# grids_v02.net
KiCad netlist of a schematic drawn in EAGLE
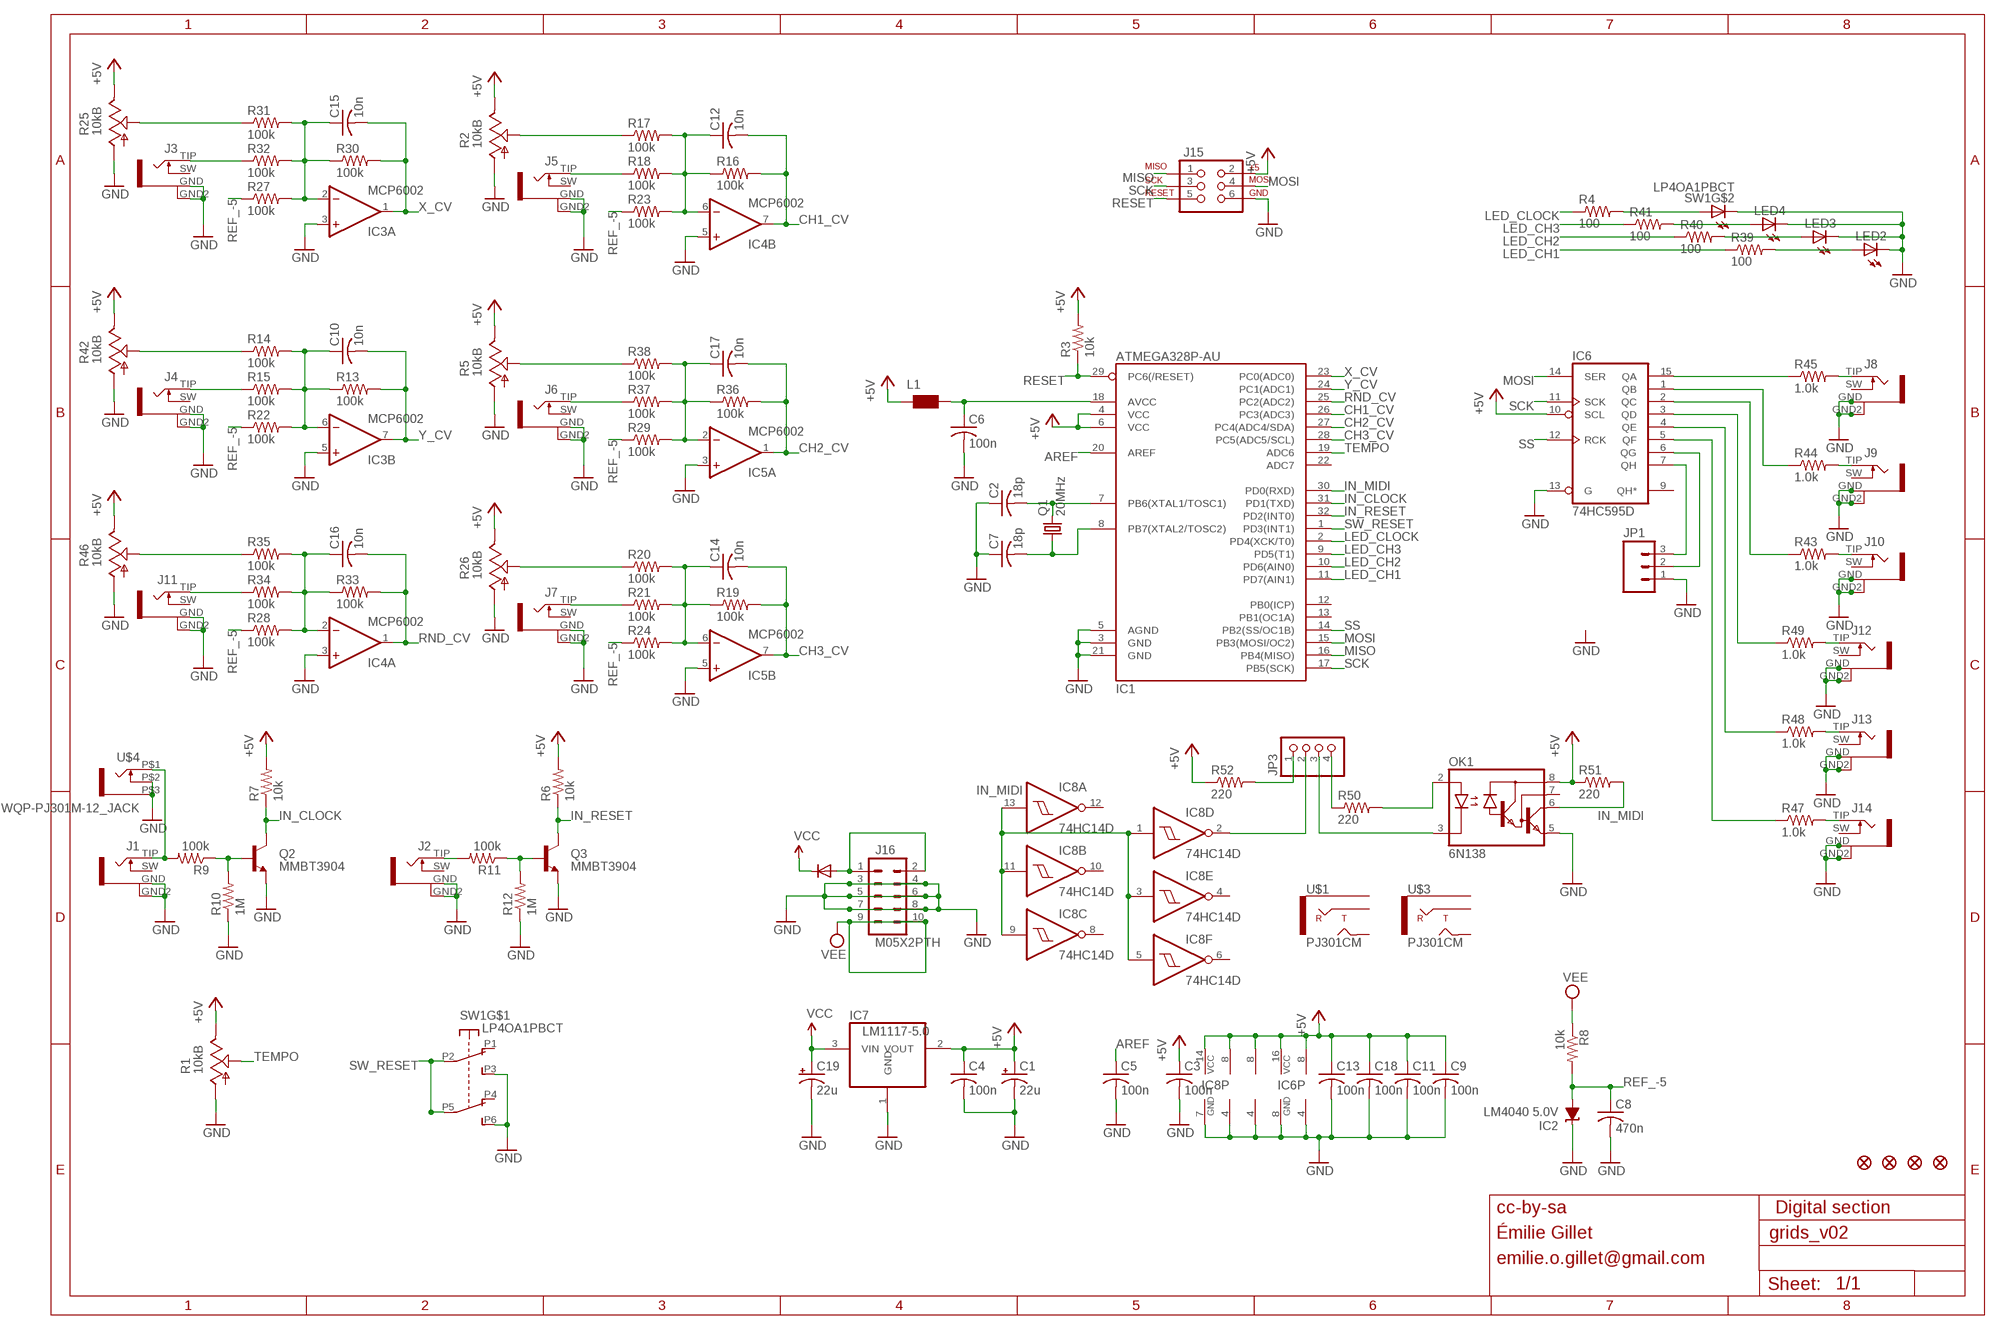
[diagram p0: schematic, sheet 1]

(export (version "E")
  (design (tool "Eeschema 10.0.6"))
  (components
    (comp (ref "C1")
      (value "22u")
      (footprint "eagle-import:PANASONIC_C")
      (libsource (lib "eagle-import") (part "CPOL-USC"))
    )
    (comp (ref "C2")
      (value "18p")
      (footprint "eagle-import:C0603")
      (libsource (lib "eagle-import") (part "C-USC0603"))
    )
    (comp (ref "C3")
      (value "100n")
      (footprint "eagle-import:C0603")
      (libsource (lib "eagle-import") (part "C-USC0603"))
    )
    (comp (ref "C4")
      (value "100n")
      (footprint "eagle-import:C0603")
      (libsource (lib "eagle-import") (part "C-USC0603"))
    )
    (comp (ref "C5")
      (value "100n")
      (footprint "eagle-import:C0603")
      (libsource (lib "eagle-import") (part "C-USC0603"))
    )
    (comp (ref "C6")
      (value "100n")
      (footprint "eagle-import:C0603")
      (libsource (lib "eagle-import") (part "C-USC0603"))
    )
    (comp (ref "C7")
      (value "18p")
      (footprint "eagle-import:C0603")
      (libsource (lib "eagle-import") (part "C-USC0603"))
    )
    (comp (ref "C8")
      (value "470n")
      (footprint "eagle-import:C0603")
      (libsource (lib "eagle-import") (part "C-USC0603"))
    )
    (comp (ref "C9")
      (value "100n")
      (footprint "eagle-import:C0603")
      (libsource (lib "eagle-import") (part "C-USC0603"))
    )
    (comp (ref "C10")
      (value "10n")
      (footprint "eagle-import:C0603")
      (libsource (lib "eagle-import") (part "C-USC0603"))
    )
    (comp (ref "C11")
      (value "100n")
      (footprint "eagle-import:C0603")
      (libsource (lib "eagle-import") (part "C-USC0603"))
    )
    (comp (ref "C12")
      (value "10n")
      (footprint "eagle-import:C0603")
      (libsource (lib "eagle-import") (part "C-USC0603"))
    )
    (comp (ref "C13")
      (value "100n")
      (footprint "eagle-import:C0603")
      (libsource (lib "eagle-import") (part "C-USC0603"))
    )
    (comp (ref "C14")
      (value "10n")
      (footprint "eagle-import:C0603")
      (libsource (lib "eagle-import") (part "C-USC0603"))
    )
    (comp (ref "C15")
      (value "10n")
      (footprint "eagle-import:C0603")
      (libsource (lib "eagle-import") (part "C-USC0603"))
    )
    (comp (ref "C16")
      (value "10n")
      (footprint "eagle-import:C0603")
      (libsource (lib "eagle-import") (part "C-USC0603"))
    )
    (comp (ref "C17")
      (value "10n")
      (footprint "eagle-import:C0603")
      (libsource (lib "eagle-import") (part "C-USC0603"))
    )
    (comp (ref "C18")
      (value "100n")
      (footprint "eagle-import:C0603")
      (libsource (lib "eagle-import") (part "C-USC0603"))
    )
    (comp (ref "C19")
      (value "22u")
      (footprint "eagle-import:PANASONIC_C")
      (libsource (lib "eagle-import") (part "CPOL-USC"))
    )
    (comp (ref "D1")
      (value "1N5819HW")
      (footprint "eagle-import:SOD123")
      (libsource (lib "eagle-import") (part "DIODE-SOD123"))
    )
    (comp (ref "F1")
      (value "FIDUCIAL1X2")
      (footprint "eagle-import:FIDUCIAL-1X2")
      (libsource (lib "eagle-import") (part "FIDUCIAL1X2"))
    )
    (comp (ref "F2")
      (value "FIDUCIAL1X2")
      (footprint "eagle-import:FIDUCIAL-1X2")
      (libsource (lib "eagle-import") (part "FIDUCIAL1X2"))
    )
    (comp (ref "F3")
      (value "FIDUCIAL1X2")
      (footprint "eagle-import:FIDUCIAL-1X2")
      (libsource (lib "eagle-import") (part "FIDUCIAL1X2"))
    )
    (comp (ref "F4")
      (value "FIDUCIAL1X2")
      (footprint "eagle-import:FIDUCIAL-1X2")
      (libsource (lib "eagle-import") (part "FIDUCIAL1X2"))
    )
    (comp (ref "IC1")
      (value "ATMEGA328P-AU")
      (footprint "eagle-import:TQFP32-08")
      (libsource (lib "eagle-import") (part "ATMEGA168"))
    )
    (comp (ref "IC2")
      (value "LM4040 5.0V")
      (footprint "eagle-import:DBZ_R-PDSO-G3")
      (libsource (lib "eagle-import") (part "LM4041DBZC12"))
    )
    (comp (ref "IC3")
      (value "MCP6002")
      (footprint "eagle-import:SO08")
      (libsource (lib "eagle-import") (part "TL072D"))
    )
    (comp (ref "IC4")
      (value "MCP6002")
      (footprint "eagle-import:SO08")
      (libsource (lib "eagle-import") (part "TL072D"))
    )
    (comp (ref "IC5")
      (value "MCP6002")
      (footprint "eagle-import:SO08")
      (libsource (lib "eagle-import") (part "TL072D"))
    )
    (comp (ref "IC6")
      (value "74HC595D")
      (footprint "eagle-import:SO16")
      (libsource (lib "eagle-import") (part "74595DHC"))
    )
    (comp (ref "IC7")
      (value "LM1117-5.0")
      (footprint "eagle-import:SOT223")
      (libsource (lib "eagle-import") (part "REG1117"))
    )
    (comp (ref "IC8")
      (value "74HC14D")
      (footprint "eagle-import:SO14")
      (libsource (lib "eagle-import") (part "7414DHC"))
    )
    (comp (ref "J1")
      (value "PJ301WQP")
      (footprint "eagle-import:WQP_PJ_301BM")
      (libsource (lib "eagle-import") (part "PJ301WQP"))
    )
    (comp (ref "J2")
      (value "PJ301WQP")
      (footprint "eagle-import:WQP_PJ_301BM")
      (libsource (lib "eagle-import") (part "PJ301WQP"))
    )
    (comp (ref "J3")
      (value "PJ301WQP")
      (footprint "eagle-import:WQP_PJ_301BM")
      (libsource (lib "eagle-import") (part "PJ301WQP"))
    )
    (comp (ref "J4")
      (value "PJ301WQP")
      (footprint "eagle-import:WQP_PJ_301BM")
      (libsource (lib "eagle-import") (part "PJ301WQP"))
    )
    (comp (ref "J5")
      (value "PJ301WQP")
      (footprint "eagle-import:WQP_PJ_301BM")
      (libsource (lib "eagle-import") (part "PJ301WQP"))
    )
    (comp (ref "J6")
      (value "PJ301WQP")
      (footprint "eagle-import:WQP_PJ_301BM")
      (libsource (lib "eagle-import") (part "PJ301WQP"))
    )
    (comp (ref "J7")
      (value "PJ301WQP")
      (footprint "eagle-import:WQP_PJ_301BM")
      (libsource (lib "eagle-import") (part "PJ301WQP"))
    )
    (comp (ref "J8")
      (value "PJ301WQP")
      (footprint "eagle-import:WQP_PJ_301BM")
      (libsource (lib "eagle-import") (part "PJ301WQP"))
    )
    (comp (ref "J9")
      (value "PJ301WQP")
      (footprint "eagle-import:WQP_PJ_301BM")
      (libsource (lib "eagle-import") (part "PJ301WQP"))
    )
    (comp (ref "J10")
      (value "PJ301WQP")
      (footprint "eagle-import:WQP_PJ_301BM")
      (libsource (lib "eagle-import") (part "PJ301WQP"))
    )
    (comp (ref "J11")
      (value "PJ301WQP")
      (footprint "eagle-import:WQP_PJ_301BM")
      (libsource (lib "eagle-import") (part "PJ301WQP"))
    )
    (comp (ref "J12")
      (value "PJ301WQP")
      (footprint "eagle-import:WQP_PJ_301BM")
      (libsource (lib "eagle-import") (part "PJ301WQP"))
    )
    (comp (ref "J13")
      (value "PJ301WQP")
      (footprint "eagle-import:WQP_PJ_301BM")
      (libsource (lib "eagle-import") (part "PJ301WQP"))
    )
    (comp (ref "J14")
      (value "PJ301WQP")
      (footprint "eagle-import:WQP_PJ_301BM")
      (libsource (lib "eagle-import") (part "PJ301WQP"))
    )
    (comp (ref "J15")
      (value "AVR_SPI_PRG_6PTH")
      (footprint "eagle-import:2X3")
      (libsource (lib "eagle-import") (part "AVR_SPI_PRG_6PTH"))
    )
    (comp (ref "J16")
      (value "M05X2PTH")
      (footprint "eagle-import:AVR_ICSP")
      (libsource (lib "eagle-import") (part "M05X2PTH"))
    )
    (comp (ref "JP1")
      (value "M03PTH")
      (footprint "eagle-import:1X03")
      (libsource (lib "eagle-import") (part "M03PTH"))
    )
    (comp (ref "JP3")
      (value "PINHD-1X4")
      (footprint "eagle-import:1X04")
      (libsource (lib "eagle-import") (part "PINHD-1X4"))
    )
    (comp (ref "L1")
      (value "WE-CBF_0603")
      (footprint "eagle-import:0603")
      (libsource (lib "eagle-import") (part "WE-CBF_0603"))
    )
    (comp (ref "LED2")
      (value "LED3MM")
      (footprint "eagle-import:LED3MM")
      (libsource (lib "eagle-import") (part "LED3MM"))
    )
    (comp (ref "LED3")
      (value "LED3MM")
      (footprint "eagle-import:LED3MM")
      (libsource (lib "eagle-import") (part "LED3MM"))
    )
    (comp (ref "LED4")
      (value "LED3MM")
      (footprint "eagle-import:LED3MM")
      (libsource (lib "eagle-import") (part "LED3MM"))
    )
    (comp (ref "OK1")
      (value "6N138")
      (footprint "eagle-import:DIL08")
      (fields (field (name "MF") "VISHAY/TELEFUNKEN"))
      (libsource (lib "eagle-import") (part "6N138"))
    )
    (comp (ref "Q1")
      (value "20MHz")
      (footprint "eagle-import:HC49UP")
      (libsource (lib "eagle-import") (part "CRYSTALHC49UP"))
    )
    (comp (ref "Q2")
      (value "MMBT3904")
      (footprint "eagle-import:SOT23-BEC")
      (libsource (lib "eagle-import") (part "-NPN-SOT23-BECMMBT3904LT1"))
    )
    (comp (ref "Q3")
      (value "MMBT3904")
      (footprint "eagle-import:SOT23-BEC")
      (libsource (lib "eagle-import") (part "-NPN-SOT23-BECMMBT3904LT1"))
    )
    (comp (ref "R1")
      (value "10kB")
      (footprint "eagle-import:ALPS_POT_VERTICAL_PS")
      (libsource (lib "eagle-import") (part "POT_USVERTICAL_PS"))
    )
    (comp (ref "R2")
      (value "10kB")
      (footprint "eagle-import:ALPS_POT_VERTICAL_PS")
      (libsource (lib "eagle-import") (part "POT_USVERTICAL_PS"))
    )
    (comp (ref "R3")
      (value "10k")
      (footprint "eagle-import:R0603")
      (libsource (lib "eagle-import") (part "R-US_R0603"))
    )
    (comp (ref "R4")
      (value "100")
      (footprint "eagle-import:R0603")
      (libsource (lib "eagle-import") (part "R-US_R0603"))
    )
    (comp (ref "R5")
      (value "10kB")
      (footprint "eagle-import:ALPS_POT_VERTICAL_PS")
      (libsource (lib "eagle-import") (part "POT_USVERTICAL_PS"))
    )
    (comp (ref "R6")
      (value "10k")
      (footprint "eagle-import:R0603")
      (libsource (lib "eagle-import") (part "R-US_R0603"))
    )
    (comp (ref "R7")
      (value "10k")
      (footprint "eagle-import:R0603")
      (libsource (lib "eagle-import") (part "R-US_R0603"))
    )
    (comp (ref "R8")
      (value "10k")
      (footprint "eagle-import:R0603")
      (libsource (lib "eagle-import") (part "resistor_R-US_R0603"))
    )
    (comp (ref "R9")
      (value "100k")
      (footprint "eagle-import:R0603")
      (libsource (lib "eagle-import") (part "R-US_R0603"))
    )
    (comp (ref "R10")
      (value "1M")
      (footprint "eagle-import:R0603")
      (libsource (lib "eagle-import") (part "R-US_R0603"))
    )
    (comp (ref "R11")
      (value "100k")
      (footprint "eagle-import:R0603")
      (libsource (lib "eagle-import") (part "R-US_R0603"))
    )
    (comp (ref "R12")
      (value "1M")
      (footprint "eagle-import:R0603")
      (libsource (lib "eagle-import") (part "R-US_R0603"))
    )
    (comp (ref "R13")
      (value "100k")
      (footprint "eagle-import:R0603")
      (libsource (lib "eagle-import") (part "R-US_R0603"))
    )
    (comp (ref "R14")
      (value "100k")
      (footprint "eagle-import:R0603")
      (libsource (lib "eagle-import") (part "R-US_R0603"))
    )
    (comp (ref "R15")
      (value "100k")
      (footprint "eagle-import:R0603")
      (libsource (lib "eagle-import") (part "R-US_R0603"))
    )
    (comp (ref "R16")
      (value "100k")
      (footprint "eagle-import:R0603")
      (libsource (lib "eagle-import") (part "R-US_R0603"))
    )
    (comp (ref "R17")
      (value "100k")
      (footprint "eagle-import:R0603")
      (libsource (lib "eagle-import") (part "R-US_R0603"))
    )
    (comp (ref "R18")
      (value "100k")
      (footprint "eagle-import:R0603")
      (libsource (lib "eagle-import") (part "R-US_R0603"))
    )
    (comp (ref "R19")
      (value "100k")
      (footprint "eagle-import:R0603")
      (libsource (lib "eagle-import") (part "R-US_R0603"))
    )
    (comp (ref "R20")
      (value "100k")
      (footprint "eagle-import:R0603")
      (libsource (lib "eagle-import") (part "R-US_R0603"))
    )
    (comp (ref "R21")
      (value "100k")
      (footprint "eagle-import:R0603")
      (libsource (lib "eagle-import") (part "R-US_R0603"))
    )
    (comp (ref "R22")
      (value "100k")
      (footprint "eagle-import:R0603")
      (libsource (lib "eagle-import") (part "R-US_R0603"))
    )
    (comp (ref "R23")
      (value "100k")
      (footprint "eagle-import:R0603")
      (libsource (lib "eagle-import") (part "R-US_R0603"))
    )
    (comp (ref "R24")
      (value "100k")
      (footprint "eagle-import:R0603")
      (libsource (lib "eagle-import") (part "R-US_R0603"))
    )
    (comp (ref "R25")
      (value "10kB")
      (footprint "eagle-import:ALPS_POT_VERTICAL_PS")
      (libsource (lib "eagle-import") (part "POT_USVERTICAL_PS"))
    )
    (comp (ref "R26")
      (value "10kB")
      (footprint "eagle-import:ALPS_POT_VERTICAL_PS")
      (libsource (lib "eagle-import") (part "POT_USVERTICAL_PS"))
    )
    (comp (ref "R27")
      (value "100k")
      (footprint "eagle-import:R0603")
      (libsource (lib "eagle-import") (part "R-US_R0603"))
    )
    (comp (ref "R28")
      (value "100k")
      (footprint "eagle-import:R0603")
      (libsource (lib "eagle-import") (part "R-US_R0603"))
    )
    (comp (ref "R29")
      (value "100k")
      (footprint "eagle-import:R0603")
      (libsource (lib "eagle-import") (part "R-US_R0603"))
    )
    (comp (ref "R30")
      (value "100k")
      (footprint "eagle-import:R0603")
      (libsource (lib "eagle-import") (part "R-US_R0603"))
    )
    (comp (ref "R31")
      (value "100k")
      (footprint "eagle-import:R0603")
      (libsource (lib "eagle-import") (part "R-US_R0603"))
    )
    (comp (ref "R32")
      (value "100k")
      (footprint "eagle-import:R0603")
      (libsource (lib "eagle-import") (part "R-US_R0603"))
    )
    (comp (ref "R33")
      (value "100k")
      (footprint "eagle-import:R0603")
      (libsource (lib "eagle-import") (part "R-US_R0603"))
    )
    (comp (ref "R34")
      (value "100k")
      (footprint "eagle-import:R0603")
      (libsource (lib "eagle-import") (part "R-US_R0603"))
    )
    (comp (ref "R35")
      (value "100k")
      (footprint "eagle-import:R0603")
      (libsource (lib "eagle-import") (part "R-US_R0603"))
    )
    (comp (ref "R36")
      (value "100k")
      (footprint "eagle-import:R0603")
      (libsource (lib "eagle-import") (part "R-US_R0603"))
    )
    (comp (ref "R37")
      (value "100k")
      (footprint "eagle-import:R0603")
      (libsource (lib "eagle-import") (part "R-US_R0603"))
    )
    (comp (ref "R38")
      (value "100k")
      (footprint "eagle-import:R0603")
      (libsource (lib "eagle-import") (part "R-US_R0603"))
    )
    (comp (ref "R39")
      (value "100")
      (footprint "eagle-import:R0603")
      (libsource (lib "eagle-import") (part "R-US_R0603"))
    )
    (comp (ref "R40")
      (value "100")
      (footprint "eagle-import:R0603")
      (libsource (lib "eagle-import") (part "R-US_R0603"))
    )
    (comp (ref "R41")
      (value "100")
      (footprint "eagle-import:R0603")
      (libsource (lib "eagle-import") (part "R-US_R0603"))
    )
    (comp (ref "R42")
      (value "10kB")
      (footprint "eagle-import:ALPS_POT_VERTICAL_PS4")
      (libsource (lib "eagle-import") (part "POT_USVERTICAL_PS4"))
    )
    (comp (ref "R43")
      (value "1.0k")
      (footprint "eagle-import:R0603")
      (libsource (lib "eagle-import") (part "R-US_R0603"))
    )
    (comp (ref "R44")
      (value "1.0k")
      (footprint "eagle-import:R0603")
      (libsource (lib "eagle-import") (part "R-US_R0603"))
    )
    (comp (ref "R45")
      (value "1.0k")
      (footprint "eagle-import:R0603")
      (libsource (lib "eagle-import") (part "R-US_R0603"))
    )
    (comp (ref "R46")
      (value "10kB")
      (footprint "eagle-import:ALPS_POT_VERTICAL_PS")
      (libsource (lib "eagle-import") (part "POT_USVERTICAL_PS"))
    )
    (comp (ref "R47")
      (value "1.0k")
      (footprint "eagle-import:R0603")
      (libsource (lib "eagle-import") (part "R-US_R0603"))
    )
    (comp (ref "R48")
      (value "1.0k")
      (footprint "eagle-import:R0603")
      (libsource (lib "eagle-import") (part "R-US_R0603"))
    )
    (comp (ref "R49")
      (value "1.0k")
      (footprint "eagle-import:R0603")
      (libsource (lib "eagle-import") (part "R-US_R0603"))
    )
    (comp (ref "R50")
      (value "220")
      (footprint "eagle-import:R0603")
      (libsource (lib "eagle-import") (part "R-US_R0603"))
    )
    (comp (ref "R51")
      (value "220")
      (footprint "eagle-import:R0603")
      (libsource (lib "eagle-import") (part "R-US_R0603"))
    )
    (comp (ref "R52")
      (value "220")
      (footprint "eagle-import:R0603")
      (libsource (lib "eagle-import") (part "R-US_R0603"))
    )
    (comp (ref "SW1")
      (value "LP4OA1PBCT")
      (footprint "eagle-import:LP4OA1PBCT")
      (libsource (lib "eagle-import") (part "LP4OA1PBCT"))
    )
    (comp (ref "U$1")
      (value "PJ301CM")
      (footprint "eagle-import:PJ301CM")
      (libsource (lib "eagle-import") (part "PJ301CM"))
    )
    (comp (ref "U$3")
      (value "PJ301CM")
      (footprint "eagle-import:PJ301CM")
      (libsource (lib "eagle-import") (part "PJ301CM"))
    )
    (comp (ref "U$4")
      (value "WQP-PJ301M-12_JACK")
      (footprint "eagle-import:WQP-PJ301M-12_JACK")
      (libsource (lib "eagle-import") (part "WQP-PJ301M-12_JACK"))
    )
  )
  (nets
    (net (code "1") (name "+5V") (class "Default")
      (node (ref "C1") (pin "+") (pinfunction "+_+") (pintype "passive"))
      (node (ref "C11") (pin "1") (pinfunction "1_1") (pintype "passive"))
      (node (ref "C13") (pin "1") (pinfunction "1_1") (pintype "passive"))
      (node (ref "C18") (pin "1") (pinfunction "1_1") (pintype "passive"))
      (node (ref "C3") (pin "1") (pinfunction "1_1") (pintype "passive"))
      (node (ref "C4") (pin "1") (pinfunction "1_1") (pintype "passive"))
      (node (ref "C9") (pin "1") (pinfunction "1_1") (pintype "passive"))
      (node (ref "IC1") (pin "4") (pinfunction "VCC_4") (pintype "bidirectional"))
      (node (ref "IC1") (pin "6") (pinfunction "VCC_6") (pintype "bidirectional"))
      (node (ref "IC3") (pin "8") (pinfunction "V+_8") (pintype "power_in"))
      (node (ref "IC4") (pin "8") (pinfunction "V+_8") (pintype "power_in"))
      (node (ref "IC5") (pin "8") (pinfunction "V+_8") (pintype "power_in"))
      (node (ref "IC6") (pin "10") (pinfunction "SCL_10") (pintype "input"))
      (node (ref "IC6") (pin "16") (pinfunction "VCC_16") (pintype "power_in"))
      (node (ref "IC7") (pin "2") (pinfunction "VOUT_2") (pintype "output"))
      (node (ref "IC8") (pin "14") (pinfunction "VCC_14") (pintype "power_in"))
      (node (ref "J15") (pin "2") (pinfunction "2_2") (pintype "passive"))
      (node (ref "L1") (pin "1") (pinfunction "1_1") (pintype "passive"))
      (node (ref "OK1") (pin "8") (pinfunction "VCC_8") (pintype "passive"))
      (node (ref "R1") (pin "P$1") (pinfunction "E_P$1") (pintype "passive"))
      (node (ref "R2") (pin "P$1") (pinfunction "E_P$1") (pintype "passive"))
      (node (ref "R25") (pin "P$1") (pinfunction "E_P$1") (pintype "passive"))
      (node (ref "R26") (pin "P$1") (pinfunction "E_P$1") (pintype "passive"))
      (node (ref "R3") (pin "2") (pinfunction "2_2") (pintype "passive"))
      (node (ref "R42") (pin "P$1") (pinfunction "E_P$1") (pintype "passive"))
      (node (ref "R46") (pin "P$1") (pinfunction "E_P$1") (pintype "passive"))
      (node (ref "R5") (pin "P$1") (pinfunction "E_P$1") (pintype "passive"))
      (node (ref "R51") (pin "1") (pinfunction "1_1") (pintype "passive"))
      (node (ref "R52") (pin "1") (pinfunction "1_1") (pintype "passive"))
      (node (ref "R6") (pin "2") (pinfunction "2_2") (pintype "passive"))
      (node (ref "R7") (pin "2") (pinfunction "2_2") (pintype "passive"))
    )
    (net (code "2") (name "/AREF") (class "Default")
      (node (ref "C5") (pin "1") (pinfunction "1_1") (pintype "passive"))
      (node (ref "IC1") (pin "20") (pinfunction "AREF_20") (pintype "bidirectional"))
    )
    (net (code "3") (name "/CH1_CV") (class "Default")
      (node (ref "C12") (pin "2") (pinfunction "2_2") (pintype "passive"))
      (node (ref "IC1") (pin "26") (pinfunction "PC3(ADC3)_26") (pintype "bidirectional"))
      (node (ref "IC4") (pin "7") (pinfunction "OUT_7") (pintype "output"))
      (node (ref "R16") (pin "2") (pinfunction "2_2") (pintype "passive"))
    )
    (net (code "4") (name "/CH2_CV") (class "Default")
      (node (ref "C17") (pin "2") (pinfunction "2_2") (pintype "passive"))
      (node (ref "IC1") (pin "27") (pinfunction "PC4(ADC4/SDA)_27") (pintype "bidirectional"))
      (node (ref "IC5") (pin "1") (pinfunction "OUT_1") (pintype "output"))
      (node (ref "R36") (pin "2") (pinfunction "2_2") (pintype "passive"))
    )
    (net (code "5") (name "/CH3_CV") (class "Default")
      (node (ref "C14") (pin "2") (pinfunction "2_2") (pintype "passive"))
      (node (ref "IC1") (pin "28") (pinfunction "PC5(ADC5/SCL)_28") (pintype "bidirectional"))
      (node (ref "IC5") (pin "7") (pinfunction "OUT_7") (pintype "output"))
      (node (ref "R19") (pin "2") (pinfunction "2_2") (pintype "passive"))
    )
    (net (code "6") (name "/IN_CLOCK") (class "Default")
      (node (ref "IC1") (pin "31") (pinfunction "PD1(TXD)_31") (pintype "bidirectional"))
      (node (ref "Q2") (pin "C") (pinfunction "C_C") (pintype "passive"))
      (node (ref "R7") (pin "1") (pinfunction "1_1") (pintype "passive"))
    )
    (net (code "7") (name "/IN_MIDI") (class "Default")
      (node (ref "IC1") (pin "30") (pinfunction "PD0(RXD)_30") (pintype "bidirectional"))
      (node (ref "IC8") (pin "1") (pinfunction "I_1") (pintype "input"))
      (node (ref "IC8") (pin "11") (pinfunction "I_11") (pintype "input"))
      (node (ref "IC8") (pin "13") (pinfunction "I_13") (pintype "input"))
      (node (ref "IC8") (pin "3") (pinfunction "I_3") (pintype "input"))
      (node (ref "IC8") (pin "5") (pinfunction "I_5") (pintype "input"))
      (node (ref "IC8") (pin "9") (pinfunction "I_9") (pintype "input"))
      (node (ref "OK1") (pin "6") (pinfunction "VO_6") (pintype "passive"))
      (node (ref "R51") (pin "2") (pinfunction "2_2") (pintype "passive"))
    )
    (net (code "8") (name "/IN_RESET") (class "Default")
      (node (ref "IC1") (pin "32") (pinfunction "PD2(INT0)_32") (pintype "bidirectional"))
      (node (ref "Q3") (pin "C") (pinfunction "C_C") (pintype "passive"))
      (node (ref "R6") (pin "1") (pinfunction "1_1") (pintype "passive"))
    )
    (net (code "9") (name "/LED_CH1") (class "Default")
      (node (ref "IC1") (pin "11") (pinfunction "PD7(AIN1)_11") (pintype "bidirectional"))
      (node (ref "R39") (pin "1") (pinfunction "1_1") (pintype "passive"))
    )
    (net (code "10") (name "/LED_CH2") (class "Default")
      (node (ref "IC1") (pin "10") (pinfunction "PD6(AIN0)_10") (pintype "bidirectional"))
      (node (ref "R40") (pin "1") (pinfunction "1_1") (pintype "passive"))
    )
    (net (code "11") (name "/LED_CH3") (class "Default")
      (node (ref "IC1") (pin "9") (pinfunction "PD5(T1)_9") (pintype "bidirectional"))
      (node (ref "R41") (pin "1") (pinfunction "1_1") (pintype "passive"))
    )
    (net (code "12") (name "/LED_CLOCK") (class "Default")
      (node (ref "IC1") (pin "2") (pinfunction "PD4(XCK/T0)_2") (pintype "bidirectional"))
      (node (ref "R4") (pin "1") (pinfunction "1_1") (pintype "passive"))
    )
    (net (code "13") (name "/MISO") (class "Default")
      (node (ref "IC1") (pin "16") (pinfunction "PB4(MISO)_16") (pintype "bidirectional"))
      (node (ref "J15") (pin "1") (pinfunction "1_1") (pintype "passive"))
    )
    (net (code "14") (name "/MOSI") (class "Default")
      (node (ref "IC1") (pin "15") (pinfunction "PB3(MOSI/OC2)_15") (pintype "bidirectional"))
      (node (ref "IC6") (pin "14") (pinfunction "SER_14") (pintype "input"))
      (node (ref "J15") (pin "4") (pinfunction "4_4") (pintype "passive"))
    )
    (net (code "15") (name "/REF_-5") (class "Default")
      (node (ref "C8") (pin "1") (pinfunction "1_1") (pintype "passive"))
      (node (ref "IC2") (pin "2") (pinfunction "A_2") (pintype "passive"))
      (node (ref "R22") (pin "1") (pinfunction "1_1") (pintype "passive"))
      (node (ref "R23") (pin "1") (pinfunction "1_1") (pintype "passive"))
      (node (ref "R24") (pin "1") (pinfunction "1_1") (pintype "passive"))
      (node (ref "R27") (pin "1") (pinfunction "1_1") (pintype "passive"))
      (node (ref "R28") (pin "1") (pinfunction "1_1") (pintype "passive"))
      (node (ref "R29") (pin "1") (pinfunction "1_1") (pintype "passive"))
      (node (ref "R8") (pin "2") (pinfunction "2_2") (pintype "passive"))
    )
    (net (code "16") (name "/RESET") (class "Default")
      (node (ref "IC1") (pin "29") (pinfunction "PC6(/RESET)_29") (pintype "bidirectional"))
      (node (ref "J15") (pin "5") (pinfunction "5_5") (pintype "passive"))
      (node (ref "R3") (pin "1") (pinfunction "1_1") (pintype "passive"))
    )
    (net (code "17") (name "/RND_CV") (class "Default")
      (node (ref "C16") (pin "2") (pinfunction "2_2") (pintype "passive"))
      (node (ref "IC1") (pin "25") (pinfunction "PC2(ADC2)_25") (pintype "bidirectional"))
      (node (ref "IC4") (pin "1") (pinfunction "OUT_1") (pintype "output"))
      (node (ref "R33") (pin "2") (pinfunction "2_2") (pintype "passive"))
    )
    (net (code "18") (name "/SCK") (class "Default")
      (node (ref "IC1") (pin "17") (pinfunction "PB5(SCK)_17") (pintype "bidirectional"))
      (node (ref "IC6") (pin "11") (pinfunction "SCK_11") (pintype "input"))
      (node (ref "J15") (pin "3") (pinfunction "3_3") (pintype "passive"))
    )
    (net (code "19") (name "/SS") (class "Default")
      (node (ref "IC1") (pin "14") (pinfunction "PB2(SS/OC1B)_14") (pintype "bidirectional"))
      (node (ref "IC6") (pin "12") (pinfunction "RCK_12") (pintype "input"))
    )
    (net (code "20") (name "/SW_RESET") (class "Default")
      (node (ref "IC1") (pin "1") (pinfunction "PD3(INT1)_1") (pintype "bidirectional"))
      (node (ref "SW1") (pin "P2") (pinfunction "A2_P2") (pintype "passive"))
      (node (ref "SW1") (pin "P5") (pinfunction "B2_P5") (pintype "passive"))
    )
    (net (code "21") (name "/TEMPO") (class "Default")
      (node (ref "IC1") (pin "19") (pinfunction "ADC6_19") (pintype "bidirectional"))
      (node (ref "R1") (pin "P$2") (pinfunction "S_P$2") (pintype "passive"))
    )
    (net (code "22") (name "/X_CV") (class "Default")
      (node (ref "C15") (pin "2") (pinfunction "2_2") (pintype "passive"))
      (node (ref "IC1") (pin "23") (pinfunction "PC0(ADC0)_23") (pintype "bidirectional"))
      (node (ref "IC3") (pin "1") (pinfunction "OUT_1") (pintype "output"))
      (node (ref "R30") (pin "2") (pinfunction "2_2") (pintype "passive"))
    )
    (net (code "23") (name "/Y_CV") (class "Default")
      (node (ref "C10") (pin "2") (pinfunction "2_2") (pintype "passive"))
      (node (ref "IC1") (pin "24") (pinfunction "PC1(ADC1)_24") (pintype "bidirectional"))
      (node (ref "IC3") (pin "7") (pinfunction "OUT_7") (pintype "output"))
      (node (ref "R13") (pin "2") (pinfunction "2_2") (pintype "passive"))
    )
    (net (code "24") (name "GND") (class "Default")
      (node (ref "C1") (pin "-") (pinfunction "-_-") (pintype "passive"))
      (node (ref "C11") (pin "2") (pinfunction "2_2") (pintype "passive"))
      (node (ref "C13") (pin "2") (pinfunction "2_2") (pintype "passive"))
      (node (ref "C18") (pin "2") (pinfunction "2_2") (pintype "passive"))
      (node (ref "C19") (pin "-") (pinfunction "-_-") (pintype "passive"))
      (node (ref "C2") (pin "1") (pinfunction "1_1") (pintype "passive"))
      (node (ref "C3") (pin "2") (pinfunction "2_2") (pintype "passive"))
      (node (ref "C4") (pin "2") (pinfunction "2_2") (pintype "passive"))
      (node (ref "C5") (pin "2") (pinfunction "2_2") (pintype "passive"))
      (node (ref "C6") (pin "2") (pinfunction "2_2") (pintype "passive"))
      (node (ref "C7") (pin "1") (pinfunction "1_1") (pintype "passive"))
      (node (ref "C8") (pin "2") (pinfunction "2_2") (pintype "passive"))
      (node (ref "C9") (pin "2") (pinfunction "2_2") (pintype "passive"))
      (node (ref "IC1") (pin "21") (pinfunction "GND_21") (pintype "bidirectional"))
      (node (ref "IC1") (pin "3") (pinfunction "GND_3") (pintype "bidirectional"))
      (node (ref "IC1") (pin "5") (pinfunction "AGND_5") (pintype "bidirectional"))
      (node (ref "IC2") (pin "1") (pinfunction "C_1") (pintype "passive"))
      (node (ref "IC3") (pin "3") (pinfunction "+IN_3") (pintype "input"))
      (node (ref "IC3") (pin "4") (pinfunction "V-_4") (pintype "power_in"))
      (node (ref "IC3") (pin "5") (pinfunction "+IN_5") (pintype "input"))
      (node (ref "IC4") (pin "3") (pinfunction "+IN_3") (pintype "input"))
      (node (ref "IC4") (pin "4") (pinfunction "V-_4") (pintype "power_in"))
      (node (ref "IC4") (pin "5") (pinfunction "+IN_5") (pintype "input"))
      (node (ref "IC5") (pin "3") (pinfunction "+IN_3") (pintype "input"))
      (node (ref "IC5") (pin "4") (pinfunction "V-_4") (pintype "power_in"))
      (node (ref "IC5") (pin "5") (pinfunction "+IN_5") (pintype "input"))
      (node (ref "IC6") (pin "13") (pinfunction "G_13") (pintype "input"))
      (node (ref "IC6") (pin "8") (pinfunction "GND_8") (pintype "power_in"))
      (node (ref "IC7") (pin "1") (pinfunction "GND_1") (pintype "power_in"))
      (node (ref "IC8") (pin "7") (pinfunction "GND_7") (pintype "power_in"))
      (node (ref "J1") (pin "GND") (pinfunction "1_GND") (pintype "passive"))
      (node (ref "J1") (pin "GND2") (pinfunction "4_GND2") (pintype "passive"))
      (node (ref "J10") (pin "GND") (pinfunction "1_GND") (pintype "passive"))
      (node (ref "J10") (pin "GND2") (pinfunction "4_GND2") (pintype "passive"))
      (node (ref "J11") (pin "GND") (pinfunction "1_GND") (pintype "passive"))
      (node (ref "J11") (pin "GND2") (pinfunction "4_GND2") (pintype "passive"))
      (node (ref "J12") (pin "GND") (pinfunction "1_GND") (pintype "passive"))
      (node (ref "J12") (pin "GND2") (pinfunction "4_GND2") (pintype "passive"))
      (node (ref "J13") (pin "GND") (pinfunction "1_GND") (pintype "passive"))
      (node (ref "J13") (pin "GND2") (pinfunction "4_GND2") (pintype "passive"))
      (node (ref "J14") (pin "GND") (pinfunction "1_GND") (pintype "passive"))
      (node (ref "J14") (pin "GND2") (pinfunction "4_GND2") (pintype "passive"))
      (node (ref "J15") (pin "6") (pinfunction "6_6") (pintype "passive"))
      (node (ref "J16") (pin "3") (pinfunction "3_3") (pintype "passive"))
      (node (ref "J16") (pin "4") (pinfunction "4_4") (pintype "passive"))
      (node (ref "J16") (pin "5") (pinfunction "5_5") (pintype "passive"))
      (node (ref "J16") (pin "6") (pinfunction "6_6") (pintype "passive"))
      (node (ref "J16") (pin "7") (pinfunction "7_7") (pintype "passive"))
      (node (ref "J16") (pin "8") (pinfunction "8_8") (pintype "passive"))
      (node (ref "J2") (pin "GND") (pinfunction "1_GND") (pintype "passive"))
      (node (ref "J2") (pin "GND2") (pinfunction "4_GND2") (pintype "passive"))
      (node (ref "J3") (pin "GND") (pinfunction "1_GND") (pintype "passive"))
      (node (ref "J3") (pin "GND2") (pinfunction "4_GND2") (pintype "passive"))
      (node (ref "J4") (pin "GND") (pinfunction "1_GND") (pintype "passive"))
      (node (ref "J4") (pin "GND2") (pinfunction "4_GND2") (pintype "passive"))
      (node (ref "J5") (pin "GND") (pinfunction "1_GND") (pintype "passive"))
      (node (ref "J5") (pin "GND2") (pinfunction "4_GND2") (pintype "passive"))
      (node (ref "J6") (pin "GND") (pinfunction "1_GND") (pintype "passive"))
      (node (ref "J6") (pin "GND2") (pinfunction "4_GND2") (pintype "passive"))
      (node (ref "J7") (pin "GND") (pinfunction "1_GND") (pintype "passive"))
      (node (ref "J7") (pin "GND2") (pinfunction "4_GND2") (pintype "passive"))
      (node (ref "J8") (pin "GND") (pinfunction "1_GND") (pintype "passive"))
      (node (ref "J8") (pin "GND2") (pinfunction "4_GND2") (pintype "passive"))
      (node (ref "J9") (pin "GND") (pinfunction "1_GND") (pintype "passive"))
      (node (ref "J9") (pin "GND2") (pinfunction "4_GND2") (pintype "passive"))
      (node (ref "JP1") (pin "1") (pinfunction "1_1") (pintype "passive"))
      (node (ref "LED2") (pin "K") (pinfunction "C_K") (pintype "passive"))
      (node (ref "LED3") (pin "K") (pinfunction "C_K") (pintype "passive"))
      (node (ref "LED4") (pin "K") (pinfunction "C_K") (pintype "passive"))
      (node (ref "OK1") (pin "5") (pinfunction "GND_5") (pintype "passive"))
      (node (ref "Q2") (pin "E") (pinfunction "E_E") (pintype "passive"))
      (node (ref "Q3") (pin "E") (pinfunction "E_E") (pintype "passive"))
      (node (ref "R1") (pin "P$3") (pinfunction "A_P$3") (pintype "passive"))
      (node (ref "R10") (pin "1") (pinfunction "1_1") (pintype "passive"))
      (node (ref "R12") (pin "1") (pinfunction "1_1") (pintype "passive"))
      (node (ref "R2") (pin "P$3") (pinfunction "A_P$3") (pintype "passive"))
      (node (ref "R25") (pin "P$3") (pinfunction "A_P$3") (pintype "passive"))
      (node (ref "R26") (pin "P$3") (pinfunction "A_P$3") (pintype "passive"))
      (node (ref "R42") (pin "P$3") (pinfunction "A_P$3") (pintype "passive"))
      (node (ref "R46") (pin "P$3") (pinfunction "A_P$3") (pintype "passive"))
      (node (ref "R5") (pin "P$3") (pinfunction "A_P$3") (pintype "passive"))
      (node (ref "SW1") (pin "L2") (pinfunction "L2_L2") (pintype "passive"))
      (node (ref "SW1") (pin "P3") (pinfunction "A3_P3") (pintype "passive"))
      (node (ref "SW1") (pin "P6") (pinfunction "B3_P6") (pintype "passive"))
      (node (ref "U$4") (pin "P$2") (pinfunction "3_P$2") (pintype "passive"))
      (node (ref "U$4") (pin "P$3") (pinfunction "1_P$3") (pintype "passive"))
    )
    (net (code "25") (name "Net-(D1-PadA)") (class "Default")
      (node (ref "D1") (pin "A") (pinfunction "A_A") (pintype "passive"))
      (node (ref "J16") (pin "1") (pinfunction "1_1") (pintype "passive"))
      (node (ref "J16") (pin "2") (pinfunction "2_2") (pintype "passive"))
    )
    (net (code "26") (name "Net-(IC1-AVCC)") (class "Default")
      (node (ref "C6") (pin "1") (pinfunction "1_1") (pintype "passive"))
      (node (ref "IC1") (pin "18") (pinfunction "AVCC_18") (pintype "bidirectional"))
      (node (ref "L1") (pin "2") (pinfunction "2_2") (pintype "passive"))
    )
    (net (code "27") (name "Net-(IC1-PB6(XTAL1{slash}TOSC1))") (class "Default")
      (node (ref "C2") (pin "2") (pinfunction "2_2") (pintype "passive"))
      (node (ref "IC1") (pin "7") (pinfunction "PB6(XTAL1/TOSC1)_7") (pintype "bidirectional"))
      (node (ref "Q1") (pin "2") (pinfunction "2_2") (pintype "passive"))
    )
    (net (code "28") (name "Net-(IC1-PB7(XTAL2{slash}TOSC2))") (class "Default")
      (node (ref "C7") (pin "2") (pinfunction "2_2") (pintype "passive"))
      (node (ref "IC1") (pin "8") (pinfunction "PB7(XTAL2/TOSC2)_8") (pintype "bidirectional"))
      (node (ref "Q1") (pin "1") (pinfunction "1_1") (pintype "passive"))
    )
    (net (code "29") (name "Net-(IC3A--IN)") (class "Default")
      (node (ref "C15") (pin "1") (pinfunction "1_1") (pintype "passive"))
      (node (ref "IC3") (pin "2") (pinfunction "-IN_2") (pintype "input"))
      (node (ref "R27") (pin "2") (pinfunction "2_2") (pintype "passive"))
      (node (ref "R30") (pin "1") (pinfunction "1_1") (pintype "passive"))
      (node (ref "R31") (pin "2") (pinfunction "2_2") (pintype "passive"))
      (node (ref "R32") (pin "2") (pinfunction "2_2") (pintype "passive"))
    )
    (net (code "30") (name "Net-(IC3B--IN)") (class "Default")
      (node (ref "C10") (pin "1") (pinfunction "1_1") (pintype "passive"))
      (node (ref "IC3") (pin "6") (pinfunction "-IN_6") (pintype "input"))
      (node (ref "R13") (pin "1") (pinfunction "1_1") (pintype "passive"))
      (node (ref "R14") (pin "2") (pinfunction "2_2") (pintype "passive"))
      (node (ref "R15") (pin "2") (pinfunction "2_2") (pintype "passive"))
      (node (ref "R22") (pin "2") (pinfunction "2_2") (pintype "passive"))
    )
    (net (code "31") (name "Net-(IC4A--IN)") (class "Default")
      (node (ref "C16") (pin "1") (pinfunction "1_1") (pintype "passive"))
      (node (ref "IC4") (pin "2") (pinfunction "-IN_2") (pintype "input"))
      (node (ref "R28") (pin "2") (pinfunction "2_2") (pintype "passive"))
      (node (ref "R33") (pin "1") (pinfunction "1_1") (pintype "passive"))
      (node (ref "R34") (pin "2") (pinfunction "2_2") (pintype "passive"))
      (node (ref "R35") (pin "2") (pinfunction "2_2") (pintype "passive"))
    )
    (net (code "32") (name "Net-(IC4B--IN)") (class "Default")
      (node (ref "C12") (pin "1") (pinfunction "1_1") (pintype "passive"))
      (node (ref "IC4") (pin "6") (pinfunction "-IN_6") (pintype "input"))
      (node (ref "R16") (pin "1") (pinfunction "1_1") (pintype "passive"))
      (node (ref "R17") (pin "2") (pinfunction "2_2") (pintype "passive"))
      (node (ref "R18") (pin "2") (pinfunction "2_2") (pintype "passive"))
      (node (ref "R23") (pin "2") (pinfunction "2_2") (pintype "passive"))
    )
    (net (code "33") (name "Net-(IC5A--IN)") (class "Default")
      (node (ref "C17") (pin "1") (pinfunction "1_1") (pintype "passive"))
      (node (ref "IC5") (pin "2") (pinfunction "-IN_2") (pintype "input"))
      (node (ref "R29") (pin "2") (pinfunction "2_2") (pintype "passive"))
      (node (ref "R36") (pin "1") (pinfunction "1_1") (pintype "passive"))
      (node (ref "R37") (pin "2") (pinfunction "2_2") (pintype "passive"))
      (node (ref "R38") (pin "2") (pinfunction "2_2") (pintype "passive"))
    )
    (net (code "34") (name "Net-(IC5B--IN)") (class "Default")
      (node (ref "C14") (pin "1") (pinfunction "1_1") (pintype "passive"))
      (node (ref "IC5") (pin "6") (pinfunction "-IN_6") (pintype "input"))
      (node (ref "R19") (pin "1") (pinfunction "1_1") (pintype "passive"))
      (node (ref "R20") (pin "2") (pinfunction "2_2") (pintype "passive"))
      (node (ref "R21") (pin "2") (pinfunction "2_2") (pintype "passive"))
      (node (ref "R24") (pin "2") (pinfunction "2_2") (pintype "passive"))
    )
    (net (code "35") (name "Net-(IC6A-QA)") (class "Default")
      (node (ref "IC6") (pin "15") (pinfunction "QA_15") (pintype "tri_state"))
      (node (ref "R45") (pin "1") (pinfunction "1_1") (pintype "passive"))
    )
    (net (code "36") (name "Net-(IC6A-QB)") (class "Default")
      (node (ref "IC6") (pin "1") (pinfunction "QB_1") (pintype "tri_state"))
      (node (ref "R44") (pin "1") (pinfunction "1_1") (pintype "passive"))
    )
    (net (code "37") (name "Net-(IC6A-QC)") (class "Default")
      (node (ref "IC6") (pin "2") (pinfunction "QC_2") (pintype "tri_state"))
      (node (ref "R43") (pin "1") (pinfunction "1_1") (pintype "passive"))
    )
    (net (code "38") (name "Net-(IC6A-QD)") (class "Default")
      (node (ref "IC6") (pin "3") (pinfunction "QD_3") (pintype "tri_state"))
      (node (ref "R49") (pin "1") (pinfunction "1_1") (pintype "passive"))
    )
    (net (code "39") (name "Net-(IC6A-QE)") (class "Default")
      (node (ref "IC6") (pin "4") (pinfunction "QE_4") (pintype "tri_state"))
      (node (ref "R48") (pin "1") (pinfunction "1_1") (pintype "passive"))
    )
    (net (code "40") (name "Net-(IC6A-QF)") (class "Default")
      (node (ref "IC6") (pin "5") (pinfunction "QF_5") (pintype "tri_state"))
      (node (ref "R47") (pin "1") (pinfunction "1_1") (pintype "passive"))
    )
    (net (code "41") (name "Net-(IC6A-QG)") (class "Default")
      (node (ref "IC6") (pin "6") (pinfunction "QG_6") (pintype "tri_state"))
      (node (ref "JP1") (pin "2") (pinfunction "2_2") (pintype "passive"))
    )
    (net (code "42") (name "Net-(IC6A-QH)") (class "Default")
      (node (ref "IC6") (pin "7") (pinfunction "QH_7") (pintype "tri_state"))
      (node (ref "JP1") (pin "3") (pinfunction "3_3") (pintype "passive"))
    )
    (net (code "43") (name "Net-(IC8D-O)") (class "Default")
      (node (ref "IC8") (pin "2") (pinfunction "O_2") (pintype "output"))
      (node (ref "JP3") (pin "2") (pinfunction "2_2") (pintype "passive"))
    )
    (net (code "44") (name "Net-(J1-2)") (class "Default")
      (node (ref "J1") (pin "TIP") (pinfunction "2_TIP") (pintype "passive"))
      (node (ref "R9") (pin "2") (pinfunction "2_2") (pintype "passive"))
      (node (ref "U$4") (pin "P$1") (pinfunction "2_P$1") (pintype "passive"))
    )
    (net (code "45") (name "Net-(J2-2)") (class "Default")
      (node (ref "J2") (pin "TIP") (pinfunction "2_TIP") (pintype "passive"))
      (node (ref "R11") (pin "2") (pinfunction "2_2") (pintype "passive"))
    )
    (net (code "46") (name "Net-(J3-2)") (class "Default")
      (node (ref "J3") (pin "TIP") (pinfunction "2_TIP") (pintype "passive"))
      (node (ref "R32") (pin "1") (pinfunction "1_1") (pintype "passive"))
    )
    (net (code "47") (name "Net-(J4-2)") (class "Default")
      (node (ref "J4") (pin "TIP") (pinfunction "2_TIP") (pintype "passive"))
      (node (ref "R15") (pin "1") (pinfunction "1_1") (pintype "passive"))
    )
    (net (code "48") (name "Net-(J5-2)") (class "Default")
      (node (ref "J5") (pin "TIP") (pinfunction "2_TIP") (pintype "passive"))
      (node (ref "R18") (pin "1") (pinfunction "1_1") (pintype "passive"))
    )
    (net (code "49") (name "Net-(J6-2)") (class "Default")
      (node (ref "J6") (pin "TIP") (pinfunction "2_TIP") (pintype "passive"))
      (node (ref "R37") (pin "1") (pinfunction "1_1") (pintype "passive"))
    )
    (net (code "50") (name "Net-(J7-2)") (class "Default")
      (node (ref "J7") (pin "TIP") (pinfunction "2_TIP") (pintype "passive"))
      (node (ref "R21") (pin "1") (pinfunction "1_1") (pintype "passive"))
    )
    (net (code "51") (name "Net-(J8-2)") (class "Default")
      (node (ref "J8") (pin "TIP") (pinfunction "2_TIP") (pintype "passive"))
      (node (ref "R45") (pin "2") (pinfunction "2_2") (pintype "passive"))
    )
    (net (code "52") (name "Net-(J9-2)") (class "Default")
      (node (ref "J9") (pin "TIP") (pinfunction "2_TIP") (pintype "passive"))
      (node (ref "R44") (pin "2") (pinfunction "2_2") (pintype "passive"))
    )
    (net (code "53") (name "Net-(J10-2)") (class "Default")
      (node (ref "J10") (pin "TIP") (pinfunction "2_TIP") (pintype "passive"))
      (node (ref "R43") (pin "2") (pinfunction "2_2") (pintype "passive"))
    )
    (net (code "54") (name "Net-(J11-2)") (class "Default")
      (node (ref "J11") (pin "TIP") (pinfunction "2_TIP") (pintype "passive"))
      (node (ref "R34") (pin "1") (pinfunction "1_1") (pintype "passive"))
    )
    (net (code "55") (name "Net-(J12-2)") (class "Default")
      (node (ref "J12") (pin "TIP") (pinfunction "2_TIP") (pintype "passive"))
      (node (ref "R49") (pin "2") (pinfunction "2_2") (pintype "passive"))
    )
    (net (code "56") (name "Net-(J13-2)") (class "Default")
      (node (ref "J13") (pin "TIP") (pinfunction "2_TIP") (pintype "passive"))
      (node (ref "R48") (pin "2") (pinfunction "2_2") (pintype "passive"))
    )
    (net (code "57") (name "Net-(J14-2)") (class "Default")
      (node (ref "J14") (pin "TIP") (pinfunction "2_TIP") (pintype "passive"))
      (node (ref "R47") (pin "2") (pinfunction "2_2") (pintype "passive"))
    )
    (net (code "58") (name "Net-(JP3-Pad1)") (class "Default")
      (node (ref "JP3") (pin "1") (pinfunction "1_1") (pintype "passive"))
      (node (ref "R52") (pin "2") (pinfunction "2_2") (pintype "passive"))
    )
    (net (code "59") (name "Net-(JP3-Pad4)") (class "Default")
      (node (ref "JP3") (pin "4") (pinfunction "4_4") (pintype "passive"))
      (node (ref "R50") (pin "1") (pinfunction "1_1") (pintype "passive"))
    )
    (net (code "60") (name "Net-(LED2-PadA)") (class "Default")
      (node (ref "LED2") (pin "A") (pinfunction "A_A") (pintype "passive"))
      (node (ref "R39") (pin "2") (pinfunction "2_2") (pintype "passive"))
    )
    (net (code "61") (name "Net-(LED3-PadA)") (class "Default")
      (node (ref "LED3") (pin "A") (pinfunction "A_A") (pintype "passive"))
      (node (ref "R40") (pin "2") (pinfunction "2_2") (pintype "passive"))
    )
    (net (code "62") (name "Net-(LED4-PadA)") (class "Default")
      (node (ref "LED4") (pin "A") (pinfunction "A_A") (pintype "passive"))
      (node (ref "R41") (pin "2") (pinfunction "2_2") (pintype "passive"))
    )
    (net (code "63") (name "Net-(OK1-A)") (class "Default")
      (node (ref "OK1") (pin "2") (pinfunction "A_2") (pintype "passive"))
      (node (ref "R50") (pin "2") (pinfunction "2_2") (pintype "passive"))
    )
    (net (code "64") (name "Net-(OK1-C)") (class "Default")
      (node (ref "JP3") (pin "3") (pinfunction "3_3") (pintype "passive"))
      (node (ref "OK1") (pin "3") (pinfunction "C_3") (pintype "passive"))
    )
    (net (code "65") (name "Net-(Q2-PadB)") (class "Default")
      (node (ref "Q2") (pin "B") (pinfunction "B_B") (pintype "passive"))
      (node (ref "R10") (pin "2") (pinfunction "2_2") (pintype "passive"))
      (node (ref "R9") (pin "1") (pinfunction "1_1") (pintype "passive"))
    )
    (net (code "66") (name "Net-(Q3-PadB)") (class "Default")
      (node (ref "Q3") (pin "B") (pinfunction "B_B") (pintype "passive"))
      (node (ref "R11") (pin "1") (pinfunction "1_1") (pintype "passive"))
      (node (ref "R12") (pin "2") (pinfunction "2_2") (pintype "passive"))
    )
    (net (code "67") (name "Net-(R2-S)") (class "Default")
      (node (ref "R17") (pin "1") (pinfunction "1_1") (pintype "passive"))
      (node (ref "R2") (pin "P$2") (pinfunction "S_P$2") (pintype "passive"))
    )
    (net (code "68") (name "Net-(R4-Pad2)") (class "Default")
      (node (ref "R4") (pin "2") (pinfunction "2_2") (pintype "passive"))
      (node (ref "SW1") (pin "L1") (pinfunction "L1_L1") (pintype "passive"))
    )
    (net (code "69") (name "Net-(R5-S)") (class "Default")
      (node (ref "R38") (pin "1") (pinfunction "1_1") (pintype "passive"))
      (node (ref "R5") (pin "P$2") (pinfunction "S_P$2") (pintype "passive"))
    )
    (net (code "70") (name "Net-(R25-S)") (class "Default")
      (node (ref "R25") (pin "P$2") (pinfunction "S_P$2") (pintype "passive"))
      (node (ref "R31") (pin "1") (pinfunction "1_1") (pintype "passive"))
    )
    (net (code "71") (name "Net-(R26-S)") (class "Default")
      (node (ref "R20") (pin "1") (pinfunction "1_1") (pintype "passive"))
      (node (ref "R26") (pin "P$2") (pinfunction "S_P$2") (pintype "passive"))
    )
    (net (code "72") (name "Net-(R42-S)") (class "Default")
      (node (ref "R14") (pin "1") (pinfunction "1_1") (pintype "passive"))
      (node (ref "R42") (pin "P$2") (pinfunction "S_P$2") (pintype "passive"))
    )
    (net (code "73") (name "Net-(R46-S)") (class "Default")
      (node (ref "R35") (pin "1") (pinfunction "1_1") (pintype "passive"))
      (node (ref "R46") (pin "P$2") (pinfunction "S_P$2") (pintype "passive"))
    )
    (net (code "74") (name "VCC") (class "Default")
      (node (ref "C19") (pin "+") (pinfunction "+_+") (pintype "passive"))
      (node (ref "D1") (pin "C") (pinfunction "C_C") (pintype "passive"))
      (node (ref "IC7") (pin "3") (pinfunction "VIN_3") (pintype "input"))
    )
    (net (code "75") (name "VEE") (class "Default")
      (node (ref "J16") (pin "10") (pinfunction "10_10") (pintype "passive"))
      (node (ref "J16") (pin "9") (pinfunction "9_9") (pintype "passive"))
      (node (ref "R8") (pin "1") (pinfunction "1_1") (pintype "passive"))
    )
    (net (code "76") (name "unconnected-(IC1-ADC7-Pad22)") (class "Default")
      (node (ref "IC1") (pin "22") (pinfunction "ADC7_22") (pintype "bidirectional"))
    )
    (net (code "77") (name "unconnected-(IC1-PB0(ICP)-Pad12)") (class "Default")
      (node (ref "IC1") (pin "12") (pinfunction "PB0(ICP)_12") (pintype "bidirectional"))
    )
    (net (code "78") (name "unconnected-(IC1-PB1(OC1A)-Pad13)") (class "Default")
      (node (ref "IC1") (pin "13") (pinfunction "PB1(OC1A)_13") (pintype "bidirectional"))
    )
    (net (code "79") (name "unconnected-(IC6A-QH*-Pad9)") (class "Default")
      (node (ref "IC6") (pin "9") (pinfunction "QH*_9") (pintype "tri_state"))
    )
    (net (code "80") (name "unconnected-(IC8A-O-Pad12)") (class "Default")
      (node (ref "IC8") (pin "12") (pinfunction "O_12") (pintype "output"))
    )
    (net (code "81") (name "unconnected-(IC8B-O-Pad10)") (class "Default")
      (node (ref "IC8") (pin "10") (pinfunction "O_10") (pintype "output"))
    )
    (net (code "82") (name "unconnected-(IC8C-O-Pad8)") (class "Default")
      (node (ref "IC8") (pin "8") (pinfunction "O_8") (pintype "output"))
    )
    (net (code "83") (name "unconnected-(IC8E-O-Pad4)") (class "Default")
      (node (ref "IC8") (pin "4") (pinfunction "O_4") (pintype "output"))
    )
    (net (code "84") (name "unconnected-(IC8F-O-Pad6)") (class "Default")
      (node (ref "IC8") (pin "6") (pinfunction "O_6") (pintype "output"))
    )
    (net (code "85") (name "unconnected-(J1-3-PadSW)") (class "Default")
      (node (ref "J1") (pin "SW") (pinfunction "3_SW") (pintype "passive"))
    )
    (net (code "86") (name "unconnected-(J2-3-PadSW)") (class "Default")
      (node (ref "J2") (pin "SW") (pinfunction "3_SW") (pintype "passive"))
    )
    (net (code "87") (name "unconnected-(J3-3-PadSW)") (class "Default")
      (node (ref "J3") (pin "SW") (pinfunction "3_SW") (pintype "passive"))
    )
    (net (code "88") (name "unconnected-(J4-3-PadSW)") (class "Default")
      (node (ref "J4") (pin "SW") (pinfunction "3_SW") (pintype "passive"))
    )
    (net (code "89") (name "unconnected-(J5-3-PadSW)") (class "Default")
      (node (ref "J5") (pin "SW") (pinfunction "3_SW") (pintype "passive"))
    )
    (net (code "90") (name "unconnected-(J6-3-PadSW)") (class "Default")
      (node (ref "J6") (pin "SW") (pinfunction "3_SW") (pintype "passive"))
    )
    (net (code "91") (name "unconnected-(J7-3-PadSW)") (class "Default")
      (node (ref "J7") (pin "SW") (pinfunction "3_SW") (pintype "passive"))
    )
    (net (code "92") (name "unconnected-(J8-3-PadSW)") (class "Default")
      (node (ref "J8") (pin "SW") (pinfunction "3_SW") (pintype "passive"))
    )
    (net (code "93") (name "unconnected-(J9-3-PadSW)") (class "Default")
      (node (ref "J9") (pin "SW") (pinfunction "3_SW") (pintype "passive"))
    )
    (net (code "94") (name "unconnected-(J10-3-PadSW)") (class "Default")
      (node (ref "J10") (pin "SW") (pinfunction "3_SW") (pintype "passive"))
    )
    (net (code "95") (name "unconnected-(J11-3-PadSW)") (class "Default")
      (node (ref "J11") (pin "SW") (pinfunction "3_SW") (pintype "passive"))
    )
    (net (code "96") (name "unconnected-(J12-3-PadSW)") (class "Default")
      (node (ref "J12") (pin "SW") (pinfunction "3_SW") (pintype "passive"))
    )
    (net (code "97") (name "unconnected-(J13-3-PadSW)") (class "Default")
      (node (ref "J13") (pin "SW") (pinfunction "3_SW") (pintype "passive"))
    )
    (net (code "98") (name "unconnected-(J14-3-PadSW)") (class "Default")
      (node (ref "J14") (pin "SW") (pinfunction "3_SW") (pintype "passive"))
    )
    (net (code "99") (name "unconnected-(OK1-VB-Pad7)") (class "Default")
      (node (ref "OK1") (pin "7") (pinfunction "VB_7") (pintype "passive"))
    )
    (net (code "100") (name "unconnected-(SW1A-A1-PadP1)") (class "Default")
      (node (ref "SW1") (pin "P1") (pinfunction "A1_P1") (pintype "passive"))
    )
    (net (code "101") (name "unconnected-(SW1A-B1-PadP4)") (class "Default")
      (node (ref "SW1") (pin "P4") (pinfunction "B1_P4") (pintype "passive"))
    )
    (net (code "102") (name "unconnected-(U$1-EARTH-PadP$1)") (class "Default")
      (node (ref "U$1") (pin "P$1") (pinfunction "EARTH_P$1") (pintype "bidirectional"))
    )
    (net (code "103") (name "unconnected-(U$1-RING-PadP$2)") (class "Default")
      (node (ref "U$1") (pin "P$2") (pinfunction "RING_P$2") (pintype "bidirectional"))
    )
    (net (code "104") (name "unconnected-(U$1-TIP-PadP$3)") (class "Default")
      (node (ref "U$1") (pin "P$3") (pinfunction "TIP_P$3") (pintype "bidirectional"))
    )
    (net (code "105") (name "unconnected-(U$3-EARTH-PadP$1)") (class "Default")
      (node (ref "U$3") (pin "P$1") (pinfunction "EARTH_P$1") (pintype "bidirectional"))
    )
    (net (code "106") (name "unconnected-(U$3-RING-PadP$2)") (class "Default")
      (node (ref "U$3") (pin "P$2") (pinfunction "RING_P$2") (pintype "bidirectional"))
    )
    (net (code "107") (name "unconnected-(U$3-TIP-PadP$3)") (class "Default")
      (node (ref "U$3") (pin "P$3") (pinfunction "TIP_P$3") (pintype "bidirectional"))
    )
  )
)
